# SubTriggerIn.net
KiCad netlist of a schematic drawn in Altium Designer
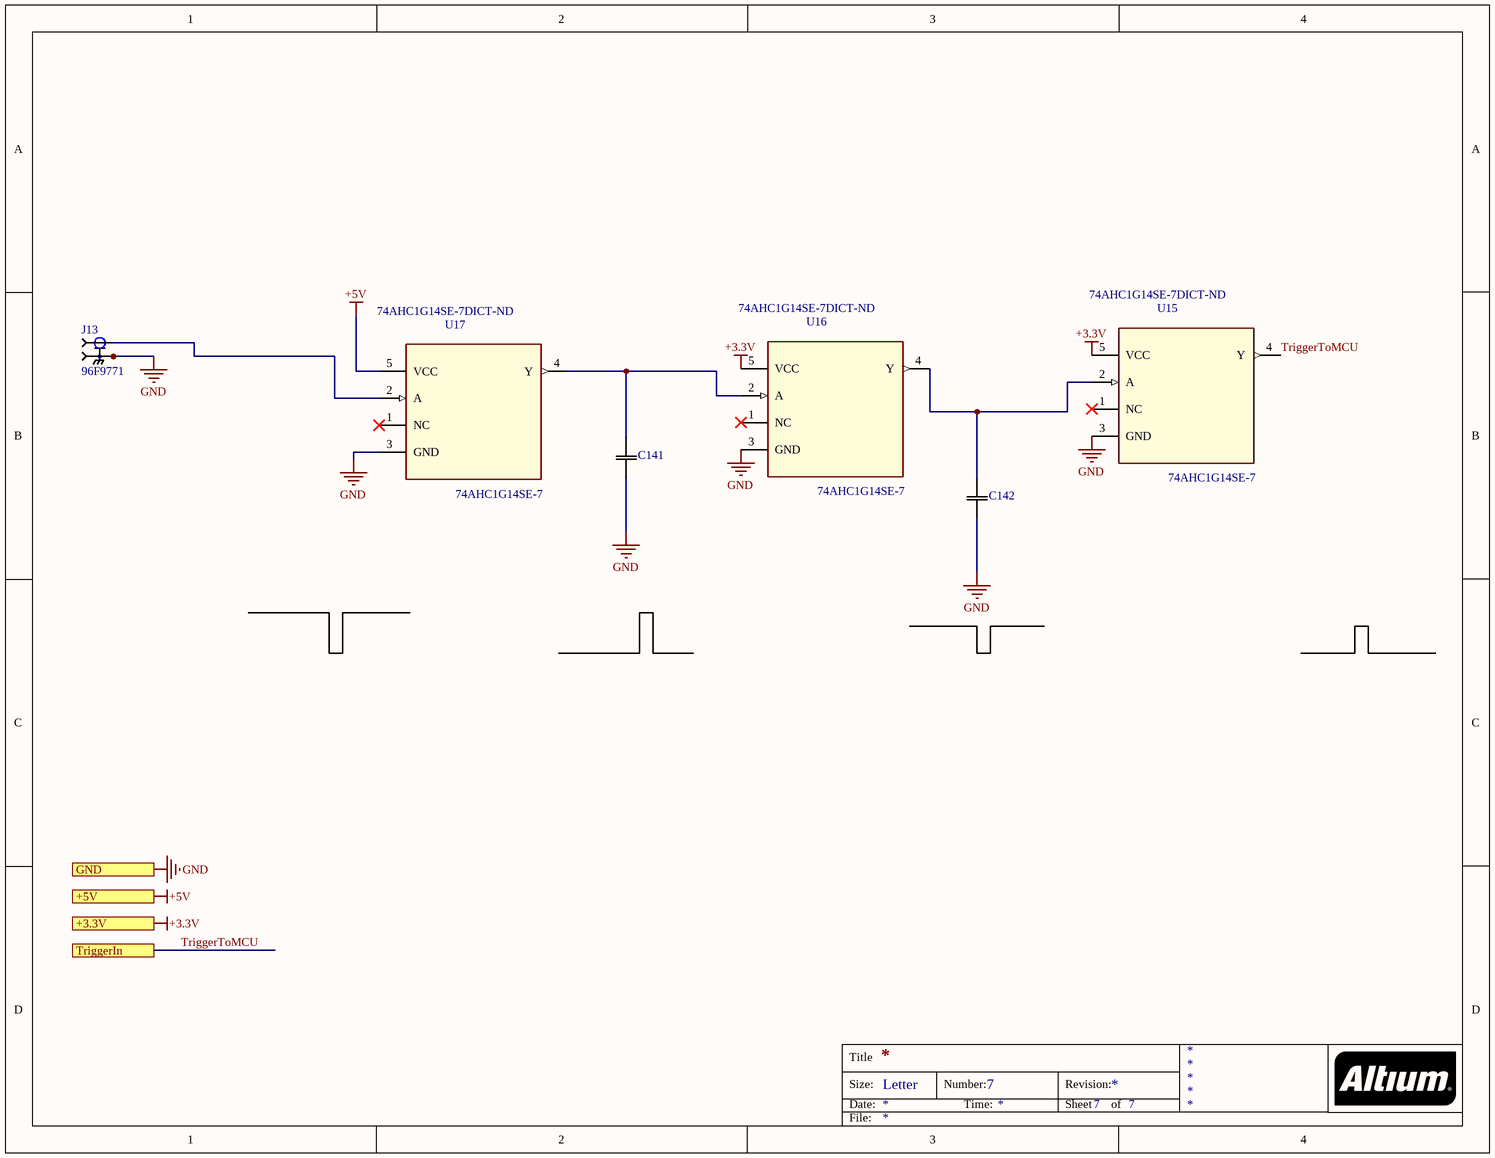
[diagram p0: SubTriggerIn.SchDoc]

(export (version "E")
  (design (tool "Eeschema 10.0.6"))
  (components
    (comp (ref "C141")
      (value "GRM155R71C103MA01D")
      (footprint "C0402")
      (libsource (lib "Afshin Library") (part "Cap_0402"))
    )
    (comp (ref "C142")
      (value "GRM155R71C103MA01D")
      (footprint "C0402")
      (libsource (lib "Afshin Library") (part "Cap_0402"))
    )
    (comp (ref "J13")
      (value "131-3701-801")
      (footprint "SMBboardEdge")
      (description "SMB Connector Jack, Male Pin 50Ohm Board Edge, End Launch Solder")
      (fields (field (name "SUPPLIER PART NUMBER 1") "96F9771"))
      (libsource (lib "Afshin Library") (part "SMB"))
    )
    (comp (ref "U15")
      (value "74AHC1G14SE-7")
      (footprint "*SOT65P210X110-5N")
      (description "Inverter IC 1 Channel Schmitt Trigger SOT-353")
      (fields
        (field (name "DIGI-KEY_PART_NUMBER") "74AHC1G14SE-7DICT-ND")
        (field (name "MF") "Diodes Inc.")
        (field (name "SUPPLIER PART NUMBER 1") "74AHC1G14SE-7DICT-ND")
      )
      (libsource (lib "Afshin Library") (part "74AHC1G14SE-7"))
    )
    (comp (ref "U16")
      (value "74AHC1G14SE-7")
      (footprint "*SOT65P210X110-5N")
      (description "Inverter IC 1 Channel Schmitt Trigger SOT-353")
      (fields
        (field (name "DIGI-KEY_PART_NUMBER") "74AHC1G14SE-7DICT-ND")
        (field (name "MF") "Diodes Inc.")
        (field (name "SUPPLIER PART NUMBER 1") "74AHC1G14SE-7DICT-ND")
      )
      (libsource (lib "Afshin Library") (part "74AHC1G14SE-7"))
    )
    (comp (ref "U17")
      (value "74AHC1G14SE-7")
      (footprint "*SOT65P210X110-5N")
      (description "Inverter IC 1 Channel Schmitt Trigger SOT-353")
      (fields
        (field (name "DIGI-KEY_PART_NUMBER") "74AHC1G14SE-7DICT-ND")
        (field (name "MF") "Diodes Inc.")
        (field (name "SUPPLIER PART NUMBER 1") "74AHC1G14SE-7DICT-ND")
      )
      (libsource (lib "Afshin Library") (part "74AHC1G14SE-7"))
    )
  )
  (nets
    (net (code "1") (name "+3.3V") (class "Default")
      (node (ref "U15") (pin "5") (pinfunction "VCC_5") (pintype "power_in"))
      (node (ref "U16") (pin "5") (pinfunction "VCC_5") (pintype "power_in"))
    )
    (net (code "2") (name "+5V") (class "Default")
      (node (ref "U17") (pin "5") (pinfunction "VCC_5") (pintype "power_in"))
    )
    (net (code "3") (name "/TriggerToMCU") (class "Default")
      (node (ref "U15") (pin "4") (pinfunction "Y_4") (pintype "output"))
    )
    (net (code "4") (name "GND") (class "Default")
      (node (ref "C141") (pin "1") (pinfunction "1_1") (pintype "passive"))
      (node (ref "C142") (pin "1") (pinfunction "1_1") (pintype "passive"))
      (node (ref "J13") (pin "SH1") (pinfunction "2_SH1") (pintype "passive"))
      (node (ref "J13") (pin "SH2") (pinfunction "2_SH2") (pintype "passive"))
      (node (ref "J13") (pin "SH3") (pinfunction "2_SH3") (pintype "passive"))
      (node (ref "J13") (pin "SH4") (pinfunction "2_SH4") (pintype "passive"))
      (node (ref "U15") (pin "3") (pinfunction "GND_3") (pintype "passive"))
      (node (ref "U16") (pin "3") (pinfunction "GND_3") (pintype "passive"))
      (node (ref "U17") (pin "3") (pinfunction "GND_3") (pintype "passive"))
    )
    (net (code "5") (name "Net-(U15-A)") (class "Default")
      (node (ref "C142") (pin "2") (pinfunction "2_2") (pintype "passive"))
      (node (ref "U15") (pin "2") (pinfunction "A_2") (pintype "input"))
      (node (ref "U16") (pin "4") (pinfunction "Y_4") (pintype "output"))
    )
    (net (code "6") (name "Net-(U16-A)") (class "Default")
      (node (ref "C141") (pin "2") (pinfunction "2_2") (pintype "passive"))
      (node (ref "U16") (pin "2") (pinfunction "A_2") (pintype "input"))
      (node (ref "U17") (pin "4") (pinfunction "Y_4") (pintype "output"))
    )
    (net (code "7") (name "Net-(U17-A)") (class "Default")
      (node (ref "J13") (pin "1") (pinfunction "1_1") (pintype "passive"))
      (node (ref "U17") (pin "2") (pinfunction "A_2") (pintype "input"))
    )
    (net (code "8") (name "unconnected-(U15-NC-Pad1)") (class "Default")
      (node (ref "U15") (pin "1") (pinfunction "NC_1") (pintype "passive+no_connect"))
    )
    (net (code "9") (name "unconnected-(U16-NC-Pad1)") (class "Default")
      (node (ref "U16") (pin "1") (pinfunction "NC_1") (pintype "passive+no_connect"))
    )
    (net (code "10") (name "unconnected-(U17-NC-Pad1)") (class "Default")
      (node (ref "U17") (pin "1") (pinfunction "NC_1") (pintype "passive+no_connect"))
    )
  )
)
